# 02_MCU.net
KiCad netlist of a schematic drawn in Altium Designer
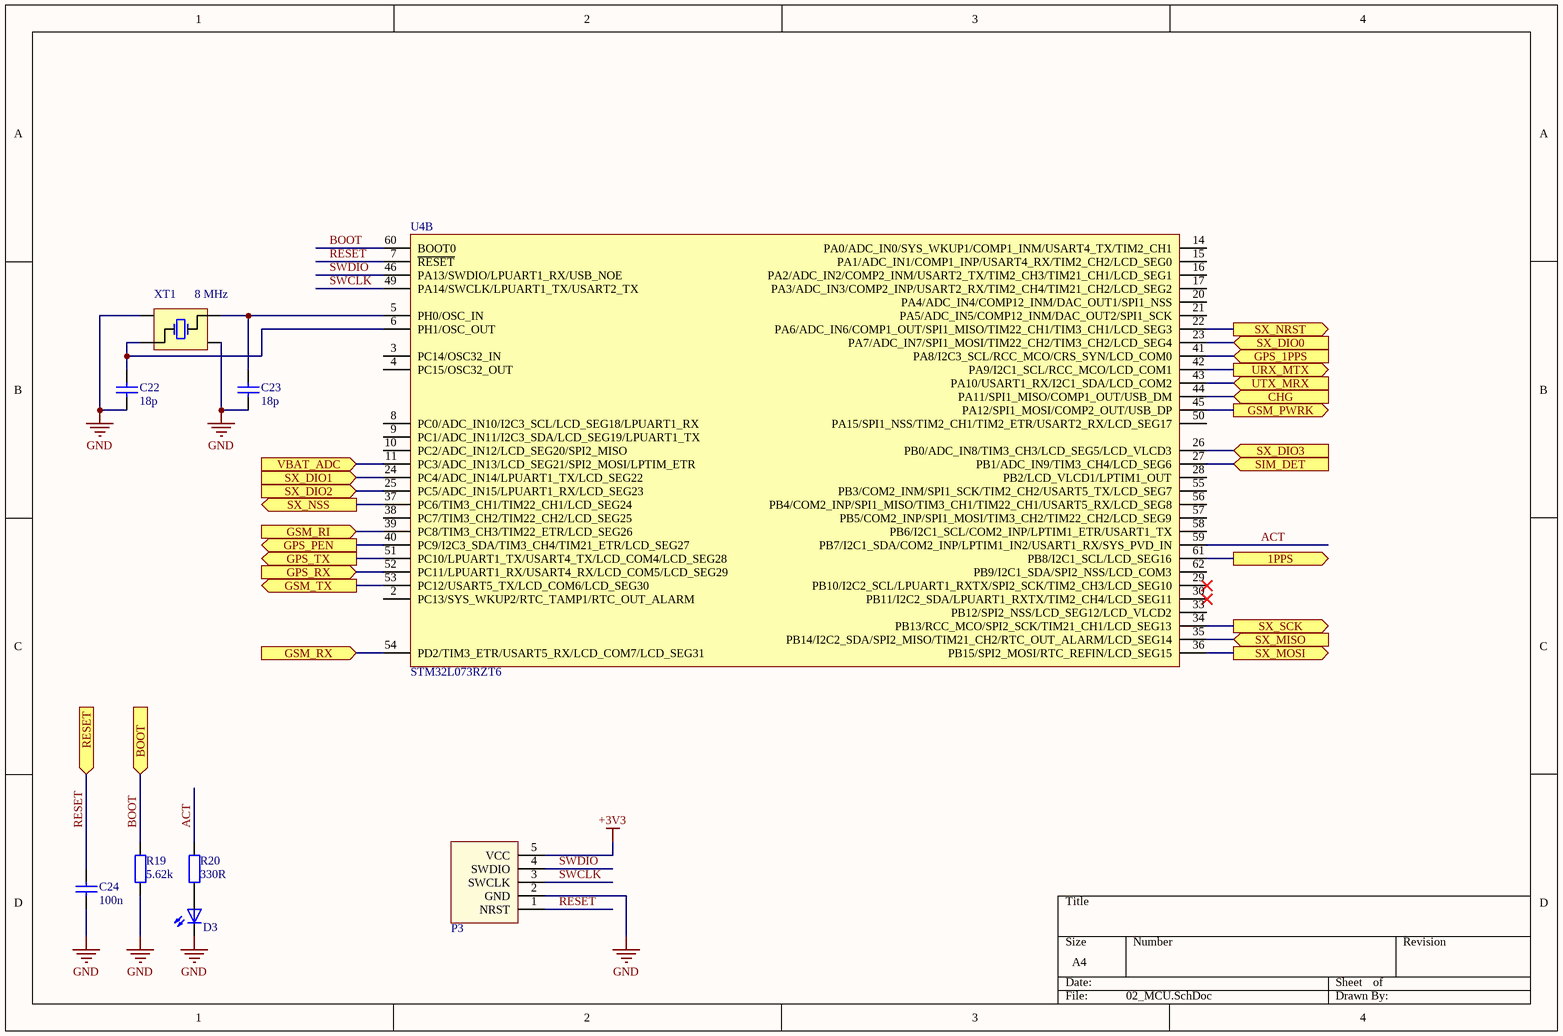
[diagram p0: 02_MCU.SchDoc]

(export (version "E")
  (design (tool "Eeschema 10.0.6"))
  (components
    (comp (ref "C22")
      (value "18p")
      (footprint "C0603_IPC_MD")
      (description "CAP CER 18PF 50V C0G/NP0 0603")
      (fields
        (field (name "MANUFACTURER") "Samsung Electro-Mechanics")
        (field (name "MANUFACTURER PART NUMBER") "CL10C180JB8NNNC")
      )
      (libsource (lib "alfasat_lib") (part "CL10C180JB8NNNC"))
    )
    (comp (ref "C23")
      (value "18p")
      (footprint "C0603_IPC_MD")
      (description "CAP CER 18PF 50V C0G/NP0 0603")
      (fields
        (field (name "MANUFACTURER") "Samsung Electro-Mechanics")
        (field (name "MANUFACTURER PART NUMBER") "CL10C180JB8NNNC")
      )
      (libsource (lib "alfasat_lib") (part "CL10C180JB8NNNC"))
    )
    (comp (ref "C24")
      (value "100n")
      (footprint "C0603_IPC_MD")
      (description "CAP CER 0.1UF 16V X7R 0603")
      (fields
        (field (name "MANUFACTURER") "Samsung Electro-Mechanics")
        (field (name "MANUFACTURER PART NUMBER") "CL10B104KO8NNNC")
      )
      (libsource (lib "alfasat_lib") (part "CL10B104KO8NNNC"))
    )
    (comp (ref "D3")
      (value "LTL-4231N")
      (footprint "LED3MM_HOLDER")
      (description "Light Emitting Diodes (LED) Green 569nm 12.6mcd@10mA Top View DIP3mm RoHS")
      (fields (field (name "MANUFACTURER") "Lite-On"))
      (libsource (lib "alfasat_lib") (part "LTL-4231N"))
    )
    (comp (ref "P3")
      (value "SWD")
      (footprint "SWD_CON_VAR2")
      (description "SWDIO SWCLK VDD GND NRST")
      (libsource (lib "alfasat_parts_lib") (part "SWD-CONNECTOR_VAR1"))
    )
    (comp (ref "R19")
      (value "5.62k")
      (footprint "R0603_IPC_MD")
      (description "RES 5.62K OHM 1% 1/10W 0603")
      (fields
        (field (name "MANUFACTURER") "Stackpole Electronics Inc")
        (field (name "MANUFACTURER PART NUMBER") "RMCF0603FT5K62")
      )
      (libsource (lib "alfasat_parts_lib") (part "CR0603-JW-5.62kR"))
    )
    (comp (ref "R20")
      (value "330R")
      (footprint "R0603_IPC_MD")
      (description "RES SMD 330 OHM 5% 1/10W 0603")
      (fields
        (field (name "MANUFACTURER") "Bourns Inc.")
        (field (name "MANUFACTURER PART NUMBER") "CR0603-JW-331ELF")
      )
      (libsource (lib "alfasat_lib") (part "CR0603-JW-331ELF"))
    )
    (comp (ref "U4")
      (value "STM32L073RZT6")
      (footprint "LQFP64_10X10MM")
      (description "Ultra-low-power 32-bit MCU ARM®-based Cortex®-M0+")
      (fields (field (name "MANUFACTURER") "ST"))
      (libsource (lib "alfasat_lib") (part "STM32L073RZT6"))
    )
    (comp (ref "XT1")
      (value "8 MHz")
      (footprint "5.0X3.2_4PAD_SMT")
      (description "8MHz ±10ppm Crystal 10pF 200 Ohms 4-SMD, No Lead")
      (fields
        (field (name "MANUFACTURER PART NUMBER") "ABM3B-8.000MHZ-10-1-U-T")
        (field (name "MANUFACTURER") "Abracon LLC")
      )
      (libsource (lib "alfasat_lib") (part "ABM3B-8.000MHZ-10-1-U-T"))
    )
  )
  (nets
    (net (code "1") (name "+3V3") (class "Default")
      (node (ref "P3") (pin "5") (pinfunction "VCC_5") (pintype "passive"))
    )
    (net (code "2") (name "/1PPS") (class "Default")
      (node (ref "U4") (pin "61") (pinfunction "PB8/I2C1_SCL/LCD_SEG16_61") (pintype "passive"))
    )
    (net (code "3") (name "/ACT") (class "Default")
      (node (ref "R20") (pin "1") (pinfunction "1_1") (pintype "passive"))
      (node (ref "U4") (pin "59") (pinfunction "PB7/I2C1_SDA/COM2_INP/LPTIM1_IN2/USART1_RX/SYS_PVD_IN_59") (pintype "passive"))
    )
    (net (code "4") (name "/BOOT") (class "Default")
      (node (ref "R19") (pin "2") (pinfunction "2_2") (pintype "passive"))
      (node (ref "U4") (pin "60") (pinfunction "BOOT0_60") (pintype "passive"))
    )
    (net (code "5") (name "/CHG") (class "Default")
      (node (ref "U4") (pin "44") (pinfunction "PA11/SPI1_MISO/COMP1_OUT/USB_DM_44") (pintype "passive"))
    )
    (net (code "6") (name "/GPS_1PPS") (class "Default")
      (node (ref "U4") (pin "41") (pinfunction "PA8/I2C3_SCL/RCC_MCO/CRS_SYN/LCD_COM0_41") (pintype "passive"))
    )
    (net (code "7") (name "/GPS_PEN") (class "Default")
      (node (ref "U4") (pin "40") (pinfunction "PC9/I2C3_SDA/TIM3_CH4/TIM21_ETR/LCD_SEG27_40") (pintype "passive"))
    )
    (net (code "8") (name "/GPS_RX") (class "Default")
      (node (ref "U4") (pin "52") (pinfunction "PC11/LPUART1_RX/USART4_RX/LCD_COM5/LCD_SEG29_52") (pintype "passive"))
    )
    (net (code "9") (name "/GPS_TX") (class "Default")
      (node (ref "U4") (pin "51") (pinfunction "PC10/LPUART1_TX/USART4_TX/LCD_COM4/LCD_SEG28_51") (pintype "passive"))
    )
    (net (code "10") (name "/GSM_PWRK") (class "Default")
      (node (ref "U4") (pin "45") (pinfunction "PA12/SPI1_MOSI/COMP2_OUT/USB_DP_45") (pintype "passive"))
    )
    (net (code "11") (name "/GSM_RI") (class "Default")
      (node (ref "U4") (pin "39") (pinfunction "PC8/TIM3_CH3/TIM22_ETR/LCD_SEG26_39") (pintype "passive"))
    )
    (net (code "12") (name "/GSM_RX") (class "Default")
      (node (ref "U4") (pin "54") (pinfunction "PD2/TIM3_ETR/USART5_RX/LCD_COM7/LCD_SEG31_54") (pintype "passive"))
    )
    (net (code "13") (name "/GSM_TX") (class "Default")
      (node (ref "U4") (pin "53") (pinfunction "PC12/USART5_TX/LCD_COM6/LCD_SEG30_53") (pintype "passive"))
    )
    (net (code "14") (name "/RESET") (class "Default")
      (node (ref "C24") (pin "2") (pinfunction "2_2") (pintype "passive"))
      (node (ref "P3") (pin "1") (pinfunction "NRST_1") (pintype "passive"))
      (node (ref "U4") (pin "7") (pinfunction "~{RESET}_7") (pintype "passive"))
    )
    (net (code "15") (name "/SIM_DET") (class "Default")
      (node (ref "U4") (pin "27") (pinfunction "PB1/ADC_IN9/TIM3_CH4/LCD_SEG6_27") (pintype "passive"))
    )
    (net (code "16") (name "/SWCLK") (class "Default")
      (node (ref "P3") (pin "3") (pinfunction "SWCLK_3") (pintype "passive"))
      (node (ref "U4") (pin "49") (pinfunction "PA14/SWCLK/LPUART1_TX/USART2_TX_49") (pintype "passive"))
    )
    (net (code "17") (name "/SWDIO") (class "Default")
      (node (ref "P3") (pin "4") (pinfunction "SWDIO_4") (pintype "passive"))
      (node (ref "U4") (pin "46") (pinfunction "PA13/SWDIO/LPUART1_RX/USB_NOE_46") (pintype "passive"))
    )
    (net (code "18") (name "/SX_DIO0") (class "Default")
      (node (ref "U4") (pin "23") (pinfunction "PA7/ADC_IN7/SPI1_MOSI/TIM22_CH2/TIM3_CH2/LCD_SEG4_23") (pintype "passive"))
    )
    (net (code "19") (name "/SX_DIO1") (class "Default")
      (node (ref "U4") (pin "24") (pinfunction "PC4/ADC_IN14/LPUART1_TX/LCD_SEG22_24") (pintype "passive"))
    )
    (net (code "20") (name "/SX_DIO2") (class "Default")
      (node (ref "U4") (pin "25") (pinfunction "PC5/ADC_IN15/LPUART1_RX/LCD_SEG23_25") (pintype "passive"))
    )
    (net (code "21") (name "/SX_DIO3") (class "Default")
      (node (ref "U4") (pin "26") (pinfunction "PB0/ADC_IN8/TIM3_CH3/LCD_SEG5/LCD_VLCD3_26") (pintype "passive"))
    )
    (net (code "22") (name "/SX_MISO") (class "Default")
      (node (ref "U4") (pin "35") (pinfunction "PB14/I2C2_SDA/SPI2_MISO/TIM21_CH2/RTC_OUT_ALARM/LCD_SEG14_35") (pintype "passive"))
    )
    (net (code "23") (name "/SX_MOSI") (class "Default")
      (node (ref "U4") (pin "36") (pinfunction "PB15/SPI2_MOSI/RTC_REFIN/LCD_SEG15_36") (pintype "passive"))
    )
    (net (code "24") (name "/SX_NRST") (class "Default")
      (node (ref "U4") (pin "22") (pinfunction "PA6/ADC_IN6/COMP1_OUT/SPI1_MISO/TIM22_CH1/TIM3_CH1/LCD_SEG3_22") (pintype "passive"))
    )
    (net (code "25") (name "/SX_NSS") (class "Default")
      (node (ref "U4") (pin "37") (pinfunction "PC6/TIM3_CH1/TIM22_CH1/LCD_SEG24_37") (pintype "passive"))
    )
    (net (code "26") (name "/SX_SCK") (class "Default")
      (node (ref "U4") (pin "34") (pinfunction "PB13/RCC_MCO/SPI2_SCK/TIM21_CH1/LCD_SEG13_34") (pintype "passive"))
    )
    (net (code "27") (name "/URX_MTX") (class "Default")
      (node (ref "U4") (pin "42") (pinfunction "PA9/I2C1_SCL/RCC_MCO/LCD_COM1_42") (pintype "passive"))
    )
    (net (code "28") (name "/UTX_MRX") (class "Default")
      (node (ref "U4") (pin "43") (pinfunction "PA10/USART1_RX/I2C1_SDA/LCD_COM2_43") (pintype "passive"))
    )
    (net (code "29") (name "/VBAT_ADC") (class "Default")
      (node (ref "U4") (pin "11") (pinfunction "PC3/ADC_IN13/LCD_SEG21/SPI2_MOSI/LPTIM_ETR_11") (pintype "passive"))
    )
    (net (code "30") (name "GND") (class "Default")
      (node (ref "C22") (pin "1") (pinfunction "1_1") (pintype "passive"))
      (node (ref "C23") (pin "1") (pinfunction "1_1") (pintype "passive"))
      (node (ref "C24") (pin "1") (pinfunction "1_1") (pintype "passive"))
      (node (ref "D3") (pin "1") (pinfunction "C_1") (pintype "passive"))
      (node (ref "P3") (pin "2") (pinfunction "GND_2") (pintype "passive"))
      (node (ref "R19") (pin "1") (pinfunction "1_1") (pintype "passive"))
      (node (ref "XT1") (pin "2") (pinfunction "NC_2") (pintype "passive"))
      (node (ref "XT1") (pin "4") (pinfunction "NC_4") (pintype "passive"))
    )
    (net (code "31") (name "Net-(D3-A)") (class "Default")
      (node (ref "D3") (pin "2") (pinfunction "A_2") (pintype "passive"))
      (node (ref "R20") (pin "2") (pinfunction "2_2") (pintype "passive"))
    )
    (net (code "32") (name "Net-(U4B-PH0{slash}OSC_IN)") (class "Default")
      (node (ref "C23") (pin "2") (pinfunction "2_2") (pintype "passive"))
      (node (ref "U4") (pin "5") (pinfunction "PH0/OSC_IN_5") (pintype "passive"))
      (node (ref "XT1") (pin "3") (pinfunction "OSC2_3") (pintype "passive"))
    )
    (net (code "33") (name "Net-(U4B-PH1{slash}OSC_OUT)") (class "Default")
      (node (ref "C22") (pin "2") (pinfunction "2_2") (pintype "passive"))
      (node (ref "U4") (pin "6") (pinfunction "PH1/OSC_OUT_6") (pintype "passive"))
      (node (ref "XT1") (pin "1") (pinfunction "OSC1_1") (pintype "passive"))
    )
    (net (code "34") (name "unconnected-(U4B-PA0{slash}ADC_IN0{slash}SYS_WKUP1{slash}COMP1_INM{slash}USART4_TX{slash}TIM2_CH1-Pad14)") (class "Default")
      (node (ref "U4") (pin "14") (pinfunction "PA0/ADC_IN0/SYS_WKUP1/COMP1_INM/USART4_TX/TIM2_CH1_14") (pintype "passive"))
    )
    (net (code "35") (name "unconnected-(U4B-PA1{slash}ADC_IN1{slash}COMP1_INP{slash}USART4_RX{slash}TIM2_CH2{slash}LCD_SEG0-Pad15)") (class "Default")
      (node (ref "U4") (pin "15") (pinfunction "PA1/ADC_IN1/COMP1_INP/USART4_RX/TIM2_CH2/LCD_SEG0_15") (pintype "passive"))
    )
    (net (code "36") (name "unconnected-(U4B-PA2{slash}ADC_IN2{slash}COMP2_INM{slash}USART2_TX{slash}TIM2_CH3{slash}TIM21_CH1{slash}LCD_SEG1-Pad16)") (class "Default")
      (node (ref "U4") (pin "16") (pinfunction "PA2/ADC_IN2/COMP2_INM/USART2_TX/TIM2_CH3/TIM21_CH1/LCD_SEG1_16") (pintype "passive"))
    )
    (net (code "37") (name "unconnected-(U4B-PA3{slash}ADC_IN3{slash}COMP2_INP{slash}USART2_RX{slash}TIM2_CH4{slash}TIM21_CH2{slash}LCD_SEG2-Pad17)") (class "Default")
      (node (ref "U4") (pin "17") (pinfunction "PA3/ADC_IN3/COMP2_INP/USART2_RX/TIM2_CH4/TIM21_CH2/LCD_SEG2_17") (pintype "passive"))
    )
    (net (code "38") (name "unconnected-(U4B-PA4{slash}ADC_IN4{slash}COMP12_INM{slash}DAC_OUT1{slash}SPI1_NSS-Pad20)") (class "Default")
      (node (ref "U4") (pin "20") (pinfunction "PA4/ADC_IN4/COMP12_INM/DAC_OUT1/SPI1_NSS_20") (pintype "passive"))
    )
    (net (code "39") (name "unconnected-(U4B-PA5{slash}ADC_IN5{slash}COMP12_INM{slash}DAC_OUT2{slash}SPI1_SCK-Pad21)") (class "Default")
      (node (ref "U4") (pin "21") (pinfunction "PA5/ADC_IN5/COMP12_INM/DAC_OUT2/SPI1_SCK_21") (pintype "passive"))
    )
    (net (code "40") (name "unconnected-(U4B-PA15{slash}SPI1_NSS{slash}TIM2_CH1{slash}TIM2_ETR{slash}USART2_RX{slash}LCD_SEG17-Pad50)") (class "Default")
      (node (ref "U4") (pin "50") (pinfunction "PA15/SPI1_NSS/TIM2_CH1/TIM2_ETR/USART2_RX/LCD_SEG17_50") (pintype "passive"))
    )
    (net (code "41") (name "unconnected-(U4B-PB2{slash}LCD_VLCD1{slash}LPTIM1_OUT-Pad28)") (class "Default")
      (node (ref "U4") (pin "28") (pinfunction "PB2/LCD_VLCD1/LPTIM1_OUT_28") (pintype "passive"))
    )
    (net (code "42") (name "unconnected-(U4B-PB3{slash}COM2_INM{slash}SPI1_SCK{slash}TIM2_CH2{slash}USART5_TX{slash}LCD_SEG7-Pad55)") (class "Default")
      (node (ref "U4") (pin "55") (pinfunction "PB3/COM2_INM/SPI1_SCK/TIM2_CH2/USART5_TX/LCD_SEG7_55") (pintype "passive"))
    )
    (net (code "43") (name "unconnected-(U4B-PB4{slash}COM2_INP{slash}SPI1_MISO{slash}TIM3_CH1{slash}TIM22_CH1{slash}USART5_RX{slash}LCD_SEG8-Pad56)") (class "Default")
      (node (ref "U4") (pin "56") (pinfunction "PB4/COM2_INP/SPI1_MISO/TIM3_CH1/TIM22_CH1/USART5_RX/LCD_SEG8_56") (pintype "passive"))
    )
    (net (code "44") (name "unconnected-(U4B-PB5{slash}COM2_INP{slash}SPI1_MOSI{slash}TIM3_CH2{slash}TIM22_CH2{slash}LCD_SEG9-Pad57)") (class "Default")
      (node (ref "U4") (pin "57") (pinfunction "PB5/COM2_INP/SPI1_MOSI/TIM3_CH2/TIM22_CH2/LCD_SEG9_57") (pintype "passive"))
    )
    (net (code "45") (name "unconnected-(U4B-PB6{slash}I2C1_SCL{slash}COM2_INP{slash}LPTIM1_ETR{slash}USART1_TX-Pad58)") (class "Default")
      (node (ref "U4") (pin "58") (pinfunction "PB6/I2C1_SCL/COM2_INP/LPTIM1_ETR/USART1_TX_58") (pintype "passive"))
    )
    (net (code "46") (name "unconnected-(U4B-PB9{slash}I2C1_SDA{slash}SPI2_NSS{slash}LCD_COM3-Pad62)") (class "Default")
      (node (ref "U4") (pin "62") (pinfunction "PB9/I2C1_SDA/SPI2_NSS/LCD_COM3_62") (pintype "passive"))
    )
    (net (code "47") (name "unconnected-(U4B-PB10{slash}I2C2_SCL{slash}LPUART1_RXTX{slash}SPI2_SCK{slash}TIM2_CH3{slash}LCD_SEG10-Pad29)") (class "Default")
      (node (ref "U4") (pin "29") (pinfunction "PB10/I2C2_SCL/LPUART1_RXTX/SPI2_SCK/TIM2_CH3/LCD_SEG10_29") (pintype "passive+no_connect"))
    )
    (net (code "48") (name "unconnected-(U4B-PB11{slash}I2C2_SDA{slash}LPUART1_RXTX{slash}TIM2_CH4{slash}LCD_SEG11-Pad30)") (class "Default")
      (node (ref "U4") (pin "30") (pinfunction "PB11/I2C2_SDA/LPUART1_RXTX/TIM2_CH4/LCD_SEG11_30") (pintype "passive+no_connect"))
    )
    (net (code "49") (name "unconnected-(U4B-PB12{slash}SPI2_NSS{slash}LCD_SEG12{slash}LCD_VLCD2-Pad33)") (class "Default")
      (node (ref "U4") (pin "33") (pinfunction "PB12/SPI2_NSS/LCD_SEG12/LCD_VLCD2_33") (pintype "passive"))
    )
    (net (code "50") (name "unconnected-(U4B-PC0{slash}ADC_IN10{slash}I2C3_SCL{slash}LCD_SEG18{slash}LPUART1_RX-Pad8)") (class "Default")
      (node (ref "U4") (pin "8") (pinfunction "PC0/ADC_IN10/I2C3_SCL/LCD_SEG18/LPUART1_RX_8") (pintype "passive"))
    )
    (net (code "51") (name "unconnected-(U4B-PC1{slash}ADC_IN11{slash}I2C3_SDA{slash}LCD_SEG19{slash}LPUART1_TX-Pad9)") (class "Default")
      (node (ref "U4") (pin "9") (pinfunction "PC1/ADC_IN11/I2C3_SDA/LCD_SEG19/LPUART1_TX_9") (pintype "passive"))
    )
    (net (code "52") (name "unconnected-(U4B-PC2{slash}ADC_IN12{slash}LCD_SEG20{slash}SPI2_MISO-Pad10)") (class "Default")
      (node (ref "U4") (pin "10") (pinfunction "PC2/ADC_IN12/LCD_SEG20/SPI2_MISO_10") (pintype "passive"))
    )
    (net (code "53") (name "unconnected-(U4B-PC7{slash}TIM3_CH2{slash}TIM22_CH2{slash}LCD_SEG25-Pad38)") (class "Default")
      (node (ref "U4") (pin "38") (pinfunction "PC7/TIM3_CH2/TIM22_CH2/LCD_SEG25_38") (pintype "passive"))
    )
    (net (code "54") (name "unconnected-(U4B-PC13{slash}SYS_WKUP2{slash}RTC_TAMP1{slash}RTC_OUT_ALARM-Pad2)") (class "Default")
      (node (ref "U4") (pin "2") (pinfunction "PC13/SYS_WKUP2/RTC_TAMP1/RTC_OUT_ALARM_2") (pintype "passive"))
    )
    (net (code "55") (name "unconnected-(U4B-PC14{slash}OSC32_IN-Pad3)") (class "Default")
      (node (ref "U4") (pin "3") (pinfunction "PC14/OSC32_IN_3") (pintype "passive"))
    )
    (net (code "56") (name "unconnected-(U4B-PC15{slash}OSC32_OUT-Pad4)") (class "Default")
      (node (ref "U4") (pin "4") (pinfunction "PC15/OSC32_OUT_4") (pintype "passive"))
    )
  )
)
